# 0HP_0ttenuator_Final.net
KiCad netlist of a schematic drawn in EAGLE
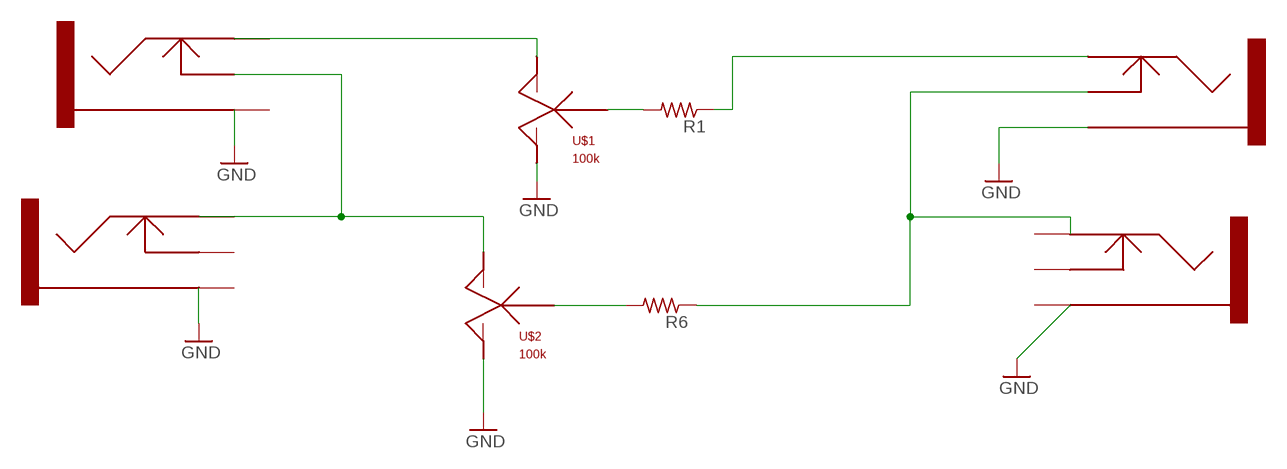
[diagram p0: schematic, sheet 1]

(export (version "E")
  (design (tool "Eeschema 10.0.6"))
  (components
    (comp (ref "CV1")
      (value "3.5MMJACK")
      (footprint "eagle-import:3.5MMPHONEJACK")
      (libsource (lib "eagle-import") (part "3.5MMJACK"))
    )
    (comp (ref "CV2")
      (value "3.5MMJACK")
      (footprint "eagle-import:3.5MMPHONEJACK")
      (libsource (lib "eagle-import") (part "3.5MMJACK"))
    )
    (comp (ref "IN")
      (value "3.5MMJACK")
      (footprint "eagle-import:3.5MMPHONEJACK")
      (libsource (lib "eagle-import") (part "3.5MMJACK"))
    )
    (comp (ref "OUT")
      (value "3.5MMJACK")
      (footprint "eagle-import:3.5MMPHONEJACK")
      (libsource (lib "eagle-import") (part "3.5MMJACK"))
    )
    (comp (ref "R1")
      (value "R-US_0207/10")
      (footprint "eagle-import:0207_10")
      (libsource (lib "eagle-import") (part "R-US_0207/10"))
    )
    (comp (ref "R6")
      (value "R-US_0207/10")
      (footprint "eagle-import:0207_10")
      (libsource (lib "eagle-import") (part "R-US_0207/10"))
    )
    (comp (ref "U$1")
      (value "100k")
      (footprint "eagle-import:ALPHAPOT_BOARDMOUNT")
      (libsource (lib "eagle-import") (part "ALPHAPOT_BOARDMOUNT"))
    )
    (comp (ref "U$2")
      (value "100k")
      (footprint "eagle-import:ALPHAPOT_BOARDMOUNT")
      (libsource (lib "eagle-import") (part "ALPHAPOT_BOARDMOUNT"))
    )
  )
  (nets
    (net (code "1") (name "GND") (class "Default")
      (node (ref "CV1") (pin "SLEEVE") (pinfunction "SLEEVE_SLEEVE") (pintype "bidirectional"))
      (node (ref "CV2") (pin "SLEEVE") (pinfunction "SLEEVE_SLEEVE") (pintype "bidirectional"))
      (node (ref "IN") (pin "SLEEVE") (pinfunction "SLEEVE_SLEEVE") (pintype "bidirectional"))
      (node (ref "OUT") (pin "SLEEVE") (pinfunction "SLEEVE_SLEEVE") (pintype "bidirectional"))
      (node (ref "U$1") (pin "RIGHT") (pinfunction "RIGHT_RIGHT") (pintype "bidirectional"))
      (node (ref "U$2") (pin "RIGHT") (pinfunction "RIGHT_RIGHT") (pintype "bidirectional"))
    )
    (net (code "2") (name "Net-(CV1-PadTIP)") (class "Default")
      (node (ref "CV1") (pin "TIP") (pinfunction "TIP_TIP") (pintype "bidirectional"))
      (node (ref "CV2") (pin "SWITCH") (pinfunction "SWITCH_SWITCH") (pintype "bidirectional"))
      (node (ref "U$2") (pin "LEFT") (pinfunction "LEFT_LEFT") (pintype "bidirectional"))
    )
    (net (code "3") (name "Net-(CV2-PadTIP)") (class "Default")
      (node (ref "CV2") (pin "TIP") (pinfunction "TIP_TIP") (pintype "bidirectional"))
      (node (ref "U$1") (pin "LEFT") (pinfunction "LEFT_LEFT") (pintype "bidirectional"))
    )
    (net (code "4") (name "Net-(IN-PadTIP)") (class "Default")
      (node (ref "IN") (pin "TIP") (pinfunction "TIP_TIP") (pintype "bidirectional"))
      (node (ref "OUT") (pin "SWITCH") (pinfunction "SWITCH_SWITCH") (pintype "bidirectional"))
      (node (ref "R6") (pin "1") (pinfunction "1_1") (pintype "passive"))
    )
    (net (code "5") (name "Net-(OUT-PadTIP)") (class "Default")
      (node (ref "OUT") (pin "TIP") (pinfunction "TIP_TIP") (pintype "bidirectional"))
      (node (ref "R1") (pin "1") (pinfunction "1_1") (pintype "passive"))
    )
    (net (code "6") (name "Net-(R1-Pad2)") (class "Default")
      (node (ref "R1") (pin "2") (pinfunction "2_2") (pintype "passive"))
      (node (ref "U$1") (pin "MID") (pinfunction "MID_MID") (pintype "bidirectional"))
    )
    (net (code "7") (name "Net-(R6-Pad2)") (class "Default")
      (node (ref "R6") (pin "2") (pinfunction "2_2") (pintype "passive"))
      (node (ref "U$2") (pin "MID") (pinfunction "MID_MID") (pintype "bidirectional"))
    )
    (net (code "8") (name "unconnected-(CV1-PadSWITCH)") (class "Default")
      (node (ref "CV1") (pin "SWITCH") (pinfunction "SWITCH_SWITCH") (pintype "bidirectional"))
    )
    (net (code "9") (name "unconnected-(IN-PadSWITCH)") (class "Default")
      (node (ref "IN") (pin "SWITCH") (pinfunction "SWITCH_SWITCH") (pintype "bidirectional"))
    )
  )
)
